# cpu.net
KiCad netlist of a schematic drawn in Altium Designer
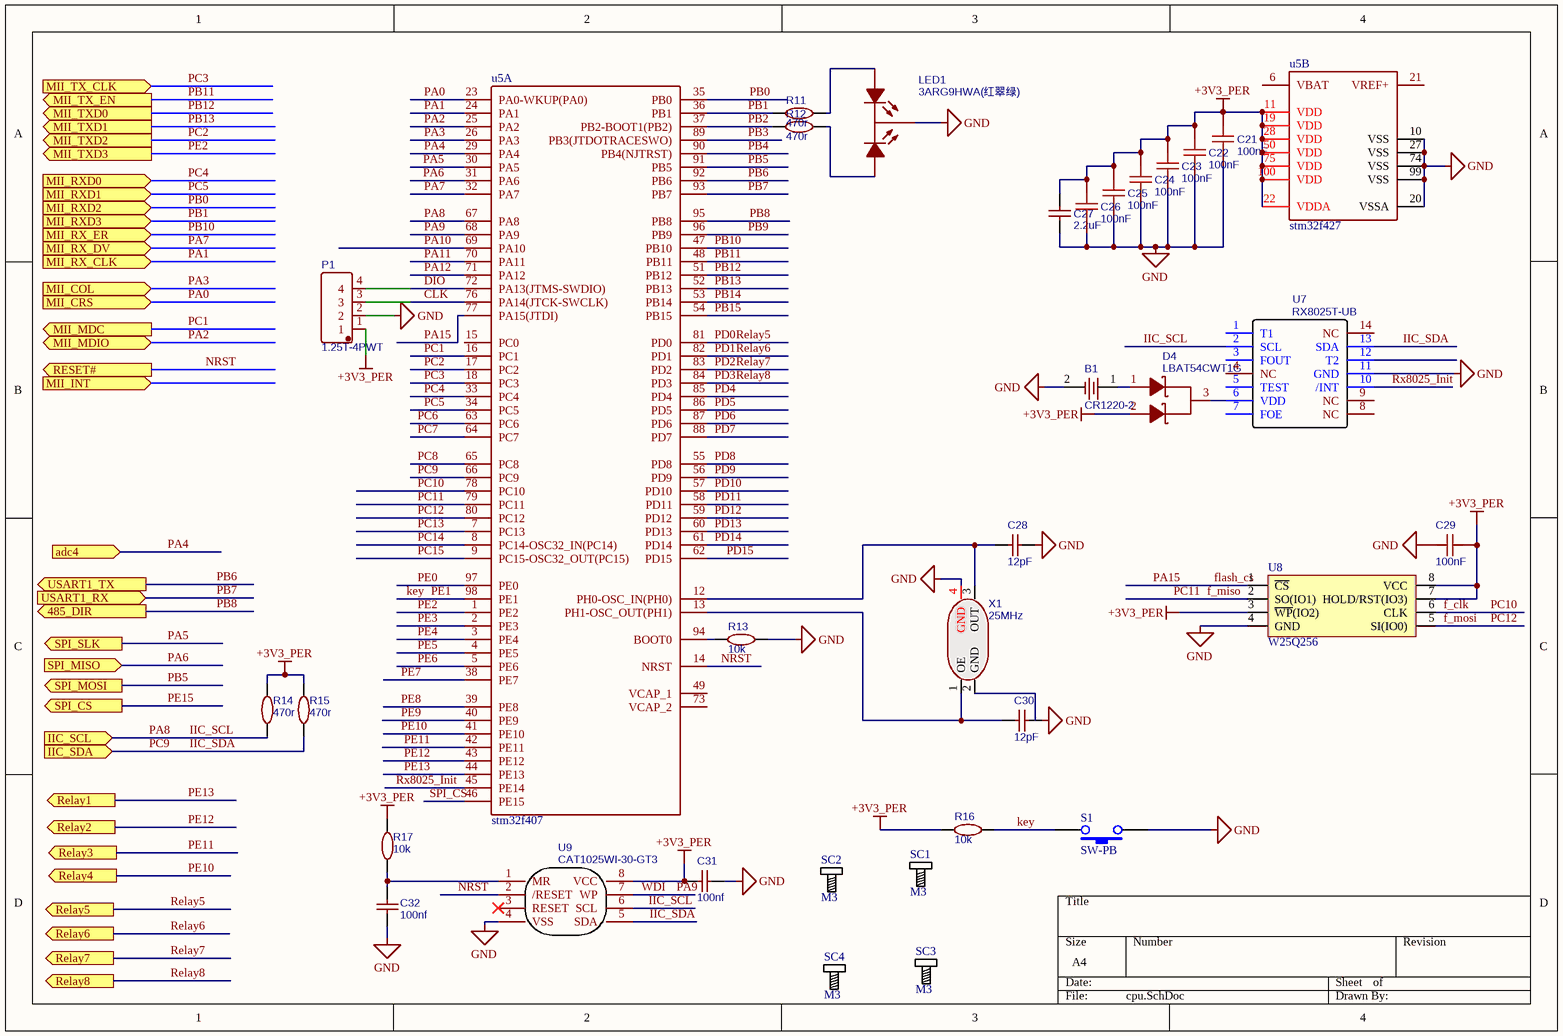
[diagram p0: cpu.SchDoc]

(export (version "E")
  (design (tool "Eeschema 10.0.6"))
  (components
    (comp (ref "B1") (value "CR1220-2") (footprint "BATTERY-2") (libsource (lib "") (part "root_2___3")))
    (comp (ref "C21")
      (value "100nF")
      (footprint "0603 - cap")
      (fields (field (name "BOM_MANUFACTURER PART") "CC0603KRX7R9BB104"))
      (libsource (lib "") (part "root_1___1"))
    )
    (comp (ref "C22")
      (value "100nF")
      (footprint "0603 - cap")
      (fields (field (name "BOM_MANUFACTURER PART") "CC0603KRX7R9BB104"))
      (libsource (lib "") (part "root_1___1"))
    )
    (comp (ref "C23")
      (value "100nF")
      (footprint "0603 - cap")
      (fields (field (name "BOM_MANUFACTURER PART") "CC0603KRX7R9BB104"))
      (libsource (lib "") (part "root_1___1"))
    )
    (comp (ref "C24")
      (value "100nF")
      (footprint "0603 - cap")
      (fields (field (name "BOM_MANUFACTURER PART") "CC0603KRX7R9BB104"))
      (libsource (lib "") (part "root_1___1"))
    )
    (comp (ref "C25")
      (value "100nF")
      (footprint "0603 - cap")
      (fields (field (name "BOM_MANUFACTURER PART") "CC0603KRX7R9BB104"))
      (libsource (lib "") (part "root_1___1"))
    )
    (comp (ref "C26")
      (value "100nF")
      (footprint "0603 - cap")
      (fields (field (name "BOM_MANUFACTURER PART") "CC0603KRX7R9BB104"))
      (libsource (lib "") (part "root_1___1"))
    )
    (comp (ref "C27")
      (value "2.2uF")
      (footprint "1206 - cap")
      (fields (field (name "BOM_MANUFACTURER PART") "CL31B225KBHNNNE"))
      (libsource (lib "altium-import") (part "root_1__"))
    )
    (comp (ref "C28")
      (value "12pF")
      (footprint "0603 - cap")
      (fields (field (name "BOM_MANUFACTURER PART") "CL10C120JB8NNNC"))
      (libsource (lib "altium-import") (part "root_2__"))
    )
    (comp (ref "C29")
      (value "100nF")
      (footprint "0603 - cap")
      (fields (field (name "BOM_MANUFACTURER PART") "CC0603KRX7R9BB104"))
      (libsource (lib "") (part "root_2___4"))
    )
    (comp (ref "C30")
      (value "12pF")
      (footprint "0603 - cap")
      (fields (field (name "BOM_MANUFACTURER PART") "CL10C120JB8NNNC"))
      (libsource (lib "altium-import") (part "root_2__"))
    )
    (comp (ref "C31")
      (value "100nf")
      (footprint "0603 - cap")
      (fields (field (name "BOM_MANUFACTURER PART") "CL10C120JB8NNNC"))
      (libsource (lib "") (part "root_0___1"))
    )
    (comp (ref "C32")
      (value "100nf")
      (footprint "0603 - cap")
      (fields (field (name "BOM_MANUFACTURER PART") "CL10C120JB8NNNC"))
      (libsource (lib "") (part "root_3___1"))
    )
    (comp (ref "D4")
      (value "LBAT54CWT1G")
      (footprint "SC-70(SC-70-3)")
      (libsource (lib "") (part "root_0___2"))
    )
    (comp (ref "LED1")
      (value "3ARG9HWA(红翠绿)")
      (footprint "led3")
      (libsource (lib "altium-import") (part "root_3__"))
    )
    (comp (ref "P1") (value "1.25T-4PWT") (footprint "1.25T-4PWT") (libsource (lib "") (part "root_2___2")))
    (comp (ref "R11")
      (value "470r")
      (footprint "0603-res")
      (fields (field (name "BOM_MANUFACTURER PART") "0603WAF1001T5E"))
      (libsource (lib "") (part "root_2___1"))
    )
    (comp (ref "R12")
      (value "470r")
      (footprint "0603-res")
      (fields (field (name "BOM_MANUFACTURER PART") "0603WAF1001T5E"))
      (libsource (lib "") (part "root_2___1"))
    )
    (comp (ref "R13")
      (value "10k")
      (footprint "0603-res")
      (fields (field (name "BOM_MANUFACTURER PART") "0603WAF1001T5E"))
      (libsource (lib "") (part "root_2___1"))
    )
    (comp (ref "R14")
      (value "470r")
      (footprint "0603-res")
      (fields (field (name "BOM_MANUFACTURER PART") "0603WAF1001T5E"))
      (libsource (lib "") (part "root_1___2"))
    )
    (comp (ref "R15")
      (value "470r")
      (footprint "0603-res")
      (fields (field (name "BOM_MANUFACTURER PART") "0603WAF1001T5E"))
      (libsource (lib "") (part "root_1___2"))
    )
    (comp (ref "R16")
      (value "10k")
      (footprint "0603-res")
      (fields (field (name "BOM_MANUFACTURER PART") "0603WAF1001T5E"))
      (libsource (lib "") (part "root_0___3"))
    )
    (comp (ref "R17")
      (value "10k")
      (footprint "0603-res")
      (fields (field (name "BOM_MANUFACTURER PART") "0603WAF1001T5E"))
      (libsource (lib "") (part "root_1___2"))
    )
    (comp (ref "S1")
      (value "SW-PB")
      (footprint "HYA45513")
      (description "微型按键开关")
      (libsource (lib "杂元件库") (part "SW-PB"))
    )
    (comp (ref "SC1")
      (value "M3")
      (footprint "安装孔(3mm)")
      (description "Screw")
      (libsource (lib "SCH_Mechanical") (part "Screw_M3"))
    )
    (comp (ref "SC2")
      (value "M3")
      (footprint "安装孔(3mm)")
      (description "Screw")
      (libsource (lib "SCH_Mechanical") (part "Screw_M3"))
    )
    (comp (ref "SC3")
      (value "M3")
      (footprint "安装孔(3mm)")
      (description "Screw")
      (libsource (lib "SCH_Mechanical") (part "Screw_M3"))
    )
    (comp (ref "SC4")
      (value "M3")
      (footprint "安装孔(3mm)")
      (description "Screw")
      (libsource (lib "SCH_Mechanical") (part "Screw_M3"))
    )
    (comp (ref "u5")
      (value "stm32f407")
      (footprint "LQFP-100_14X14X05P")
      (libsource (lib "TcpControl_1") (part "stm32f427"))
    )
    (comp (ref "U7")
      (value "RX8025T-UB")
      (footprint "SOP-14_208MIL")
      (libsource (lib "altium-import") (part "root_0__"))
    )
    (comp (ref "U8")
      (value "W25Q256")
      (footprint "LC-SOIC-8_208mil")
      (description "W25Q128")
      (libsource (lib "STM32F429核心板封装库") (part "W25Q128"))
    )
    (comp (ref "U9")
      (value "CAT1025WI-30-GT3")
      (footprint "SOIC-8_150MIL")
      (libsource (lib "") (part "root_0___4"))
    )
    (comp (ref "X1")
      (value "25MHz")
      (footprint "OSC-YSX-3225_4P")
      (fields (field (name "BOM_MANUFACTURER PART") "X322525MOB4SI"))
      (libsource (lib "") (part "root_1___3"))
    )
  )
  (nets
    (net (code "1") (name "+3V3_PER") (class "Default")
      (node (ref "C21") (pin "2") (pinfunction "2_2") (pintype "passive"))
      (node (ref "C22") (pin "2") (pinfunction "2_2") (pintype "passive"))
      (node (ref "C23") (pin "2") (pinfunction "2_2") (pintype "passive"))
      (node (ref "C24") (pin "2") (pinfunction "2_2") (pintype "passive"))
      (node (ref "C25") (pin "2") (pinfunction "2_2") (pintype "passive"))
      (node (ref "C26") (pin "2") (pinfunction "2_2") (pintype "passive"))
      (node (ref "C27") (pin "2") (pinfunction "2_2") (pintype "passive"))
      (node (ref "C29") (pin "1") (pinfunction "1_1") (pintype "passive"))
      (node (ref "C31") (pin "1") (pinfunction "1_1") (pintype "passive"))
      (node (ref "D4") (pin "2") (pinfunction "K2_2") (pintype "passive"))
      (node (ref "P1") (pin "1") (pinfunction "1_1") (pintype "passive"))
      (node (ref "R14") (pin "2") (pinfunction "2_2") (pintype "passive"))
      (node (ref "R15") (pin "2") (pinfunction "2_2") (pintype "passive"))
      (node (ref "R16") (pin "1") (pinfunction "1_1") (pintype "passive"))
      (node (ref "R17") (pin "2") (pinfunction "2_2") (pintype "passive"))
      (node (ref "U8") (pin "3") (pinfunction "~{WP}(IO2)_3") (pintype "passive"))
      (node (ref "U8") (pin "7") (pinfunction "HOLD/RST(IO3)_7") (pintype "power_in"))
      (node (ref "U8") (pin "8") (pinfunction "VCC_8") (pintype "passive"))
      (node (ref "U9") (pin "8") (pinfunction "VCC_8") (pintype "passive"))
      (node (ref "u5") (pin "100") (pinfunction "VDD_100") (pintype "passive"))
      (node (ref "u5") (pin "11") (pinfunction "VDD_11") (pintype "passive"))
      (node (ref "u5") (pin "19") (pinfunction "VDD_19") (pintype "passive"))
      (node (ref "u5") (pin "22") (pinfunction "VDDA_22") (pintype "passive"))
      (node (ref "u5") (pin "28") (pinfunction "VDD_28") (pintype "passive"))
      (node (ref "u5") (pin "50") (pinfunction "VDD_50") (pintype "passive"))
      (node (ref "u5") (pin "75") (pinfunction "VDD_75") (pintype "passive"))
    )
    (net (code "2") (name "/CLK") (class "Default")
      (node (ref "P1") (pin "3") (pinfunction "3_3") (pintype "passive"))
      (node (ref "u5") (pin "76") (pinfunction "PA14(JTCK-SWCLK)_76") (pintype "passive"))
    )
    (net (code "3") (name "/DIO") (class "Default")
      (node (ref "P1") (pin "4") (pinfunction "4_4") (pintype "passive"))
      (node (ref "u5") (pin "72") (pinfunction "PA13(JTMS-SWDIO)_72") (pintype "passive"))
    )
    (net (code "4") (name "/IIC_SCL") (class "Default")
      (node (ref "R14") (pin "1") (pinfunction "1_1") (pintype "passive"))
      (node (ref "U7") (pin "2") (pinfunction "SCL_2") (pintype "passive"))
      (node (ref "U9") (pin "6") (pinfunction "SCL_6") (pintype "passive"))
      (node (ref "u5") (pin "67") (pinfunction "PA8_67") (pintype "passive"))
    )
    (net (code "5") (name "/IIC_SDA") (class "Default")
      (node (ref "R15") (pin "1") (pinfunction "1_1") (pintype "passive"))
      (node (ref "U7") (pin "13") (pinfunction "SDA_13") (pintype "passive"))
      (node (ref "U9") (pin "5") (pinfunction "SDA_5") (pintype "passive"))
      (node (ref "u5") (pin "66") (pinfunction "PC9_66") (pintype "passive"))
    )
    (net (code "7") (name "/NRST") (class "Default")
      (node (ref "U9") (pin "2") (pinfunction "/RESET_2") (pintype "passive"))
      (node (ref "u5") (pin "14") (pinfunction "NRST_14") (pintype "passive"))
    )
    (net (code "8") (name "/PA0") (class "Default")
      (node (ref "u5") (pin "23") (pinfunction "PA0-WKUP(PA0)_23") (pintype "passive"))
    )
    (net (code "9") (name "/PA1") (class "Default")
      (node (ref "u5") (pin "24") (pinfunction "PA1_24") (pintype "passive"))
    )
    (net (code "10") (name "/PA2") (class "Default")
      (node (ref "u5") (pin "25") (pinfunction "PA2_25") (pintype "passive"))
    )
    (net (code "11") (name "/PA3") (class "Default")
      (node (ref "u5") (pin "26") (pinfunction "PA3_26") (pintype "passive"))
    )
    (net (code "12") (name "/PA4") (class "Default")
      (node (ref "u5") (pin "29") (pinfunction "PA4_29") (pintype "passive"))
    )
    (net (code "13") (name "/PA5") (class "Default")
      (node (ref "u5") (pin "30") (pinfunction "PA5_30") (pintype "passive"))
    )
    (net (code "14") (name "/PA6") (class "Default")
      (node (ref "u5") (pin "31") (pinfunction "PA6_31") (pintype "passive"))
    )
    (net (code "15") (name "/PA7") (class "Default")
      (node (ref "u5") (pin "32") (pinfunction "PA7_32") (pintype "passive"))
    )
    (net (code "16") (name "/PA9") (class "Default")
      (node (ref "U9") (pin "7") (pinfunction "WP_7") (pintype "passive"))
      (node (ref "u5") (pin "68") (pinfunction "PA9_68") (pintype "passive"))
    )
    (net (code "17") (name "/PA10") (class "Default")
      (node (ref "u5") (pin "69") (pinfunction "PA10_69") (pintype "passive"))
    )
    (net (code "18") (name "/PA11") (class "Default")
      (node (ref "u5") (pin "70") (pinfunction "PA11_70") (pintype "passive"))
    )
    (net (code "19") (name "/PA12") (class "Default")
      (node (ref "u5") (pin "71") (pinfunction "PA12_71") (pintype "passive"))
    )
    (net (code "20") (name "/PA15") (class "Default")
      (node (ref "U8") (pin "1") (pinfunction "~{CS}_1") (pintype "passive"))
      (node (ref "u5") (pin "77") (pinfunction "PA15(JTDI)_77") (pintype "passive"))
    )
    (net (code "21") (name "/PB0") (class "Default")
      (node (ref "u5") (pin "35") (pinfunction "PB0_35") (pintype "passive"))
    )
    (net (code "22") (name "/PB1") (class "Default")
      (node (ref "R11") (pin "2") (pinfunction "2_2") (pintype "passive"))
      (node (ref "u5") (pin "36") (pinfunction "PB1_36") (pintype "passive"))
    )
    (net (code "23") (name "/PB2") (class "Default")
      (node (ref "R12") (pin "2") (pinfunction "2_2") (pintype "passive"))
      (node (ref "u5") (pin "37") (pinfunction "PB2-BOOT1(PB2)_37") (pintype "passive"))
    )
    (net (code "24") (name "/PB3") (class "Default")
      (node (ref "u5") (pin "89") (pinfunction "PB3(JTDOTRACESWO)_89") (pintype "passive"))
    )
    (net (code "25") (name "/PB4") (class "Default")
      (node (ref "u5") (pin "90") (pinfunction "PB4(NJTRST)_90") (pintype "passive"))
    )
    (net (code "26") (name "/PB5") (class "Default")
      (node (ref "u5") (pin "91") (pinfunction "PB5_91") (pintype "passive"))
    )
    (net (code "27") (name "/PB6") (class "Default")
      (node (ref "u5") (pin "92") (pinfunction "PB6_92") (pintype "passive"))
    )
    (net (code "28") (name "/PB7") (class "Default")
      (node (ref "u5") (pin "93") (pinfunction "PB7_93") (pintype "passive"))
    )
    (net (code "29") (name "/PB8") (class "Default")
      (node (ref "u5") (pin "95") (pinfunction "PB8_95") (pintype "passive"))
    )
    (net (code "30") (name "/PB9") (class "Default")
      (node (ref "u5") (pin "96") (pinfunction "PB9_96") (pintype "passive"))
    )
    (net (code "31") (name "/PB10") (class "Default")
      (node (ref "u5") (pin "47") (pinfunction "PB10_47") (pintype "passive"))
    )
    (net (code "32") (name "/PB11") (class "Default")
      (node (ref "u5") (pin "48") (pinfunction "PB11_48") (pintype "passive"))
    )
    (net (code "33") (name "/PB12") (class "Default")
      (node (ref "u5") (pin "51") (pinfunction "PB12_51") (pintype "passive"))
    )
    (net (code "34") (name "/PB13") (class "Default")
      (node (ref "u5") (pin "52") (pinfunction "PB13_52") (pintype "passive"))
    )
    (net (code "35") (name "/PB14") (class "Default")
      (node (ref "u5") (pin "53") (pinfunction "PB14_53") (pintype "passive"))
    )
    (net (code "36") (name "/PB15") (class "Default")
      (node (ref "u5") (pin "54") (pinfunction "PB15_54") (pintype "passive"))
    )
    (net (code "37") (name "/PC1") (class "Default")
      (node (ref "u5") (pin "16") (pinfunction "PC1_16") (pintype "passive"))
    )
    (net (code "38") (name "/PC2") (class "Default")
      (node (ref "u5") (pin "17") (pinfunction "PC2_17") (pintype "passive"))
    )
    (net (code "39") (name "/PC3") (class "Default")
      (node (ref "u5") (pin "18") (pinfunction "PC3_18") (pintype "passive"))
    )
    (net (code "40") (name "/PC4") (class "Default")
      (node (ref "u5") (pin "33") (pinfunction "PC4_33") (pintype "passive"))
    )
    (net (code "41") (name "/PC5") (class "Default")
      (node (ref "u5") (pin "34") (pinfunction "PC5_34") (pintype "passive"))
    )
    (net (code "42") (name "/PC6") (class "Default")
      (node (ref "u5") (pin "63") (pinfunction "PC6_63") (pintype "passive"))
    )
    (net (code "43") (name "/PC7") (class "Default")
      (node (ref "u5") (pin "64") (pinfunction "PC7_64") (pintype "passive"))
    )
    (net (code "44") (name "/PC8") (class "Default")
      (node (ref "u5") (pin "65") (pinfunction "PC8_65") (pintype "passive"))
    )
    (net (code "45") (name "/PC10") (class "Default")
      (node (ref "U8") (pin "6") (pinfunction "CLK_6") (pintype "passive"))
      (node (ref "u5") (pin "78") (pinfunction "PC10_78") (pintype "passive"))
    )
    (net (code "46") (name "/PC11") (class "Default")
      (node (ref "U8") (pin "2") (pinfunction "SO(IO1)_2") (pintype "passive"))
      (node (ref "u5") (pin "79") (pinfunction "PC11_79") (pintype "passive"))
    )
    (net (code "47") (name "/PC12") (class "Default")
      (node (ref "U8") (pin "5") (pinfunction "SI(IO0)_5") (pintype "power_in"))
      (node (ref "u5") (pin "80") (pinfunction "PC12_80") (pintype "passive"))
    )
    (net (code "48") (name "/PC13") (class "Default")
      (node (ref "u5") (pin "7") (pinfunction "PC13_7") (pintype "passive"))
    )
    (net (code "49") (name "/PC14") (class "Default")
      (node (ref "u5") (pin "8") (pinfunction "PC14-OSC32_IN(PC14)_8") (pintype "passive"))
    )
    (net (code "50") (name "/PC15") (class "Default")
      (node (ref "u5") (pin "9") (pinfunction "PC15-OSC32_OUT(PC15)_9") (pintype "passive"))
    )
    (net (code "51") (name "/PD0") (class "Default")
      (node (ref "u5") (pin "81") (pinfunction "PD0_81") (pintype "passive"))
    )
    (net (code "52") (name "/PD1") (class "Default")
      (node (ref "u5") (pin "82") (pinfunction "PD1_82") (pintype "passive"))
    )
    (net (code "53") (name "/PD2") (class "Default")
      (node (ref "u5") (pin "83") (pinfunction "PD2_83") (pintype "passive"))
    )
    (net (code "54") (name "/PD3") (class "Default")
      (node (ref "u5") (pin "84") (pinfunction "PD3_84") (pintype "passive"))
    )
    (net (code "55") (name "/PD4") (class "Default")
      (node (ref "u5") (pin "85") (pinfunction "PD4_85") (pintype "passive"))
    )
    (net (code "56") (name "/PD5") (class "Default")
      (node (ref "u5") (pin "86") (pinfunction "PD5_86") (pintype "passive"))
    )
    (net (code "57") (name "/PD6") (class "Default")
      (node (ref "u5") (pin "87") (pinfunction "PD6_87") (pintype "passive"))
    )
    (net (code "58") (name "/PD7") (class "Default")
      (node (ref "u5") (pin "88") (pinfunction "PD7_88") (pintype "passive"))
    )
    (net (code "59") (name "/PD8") (class "Default")
      (node (ref "u5") (pin "55") (pinfunction "PD8_55") (pintype "passive"))
    )
    (net (code "60") (name "/PD9") (class "Default")
      (node (ref "u5") (pin "56") (pinfunction "PD9_56") (pintype "passive"))
    )
    (net (code "61") (name "/PD10") (class "Default")
      (node (ref "u5") (pin "57") (pinfunction "PD10_57") (pintype "passive"))
    )
    (net (code "62") (name "/PD11") (class "Default")
      (node (ref "u5") (pin "58") (pinfunction "PD11_58") (pintype "passive"))
    )
    (net (code "63") (name "/PD12") (class "Default")
      (node (ref "u5") (pin "59") (pinfunction "PD12_59") (pintype "passive"))
    )
    (net (code "64") (name "/PD13") (class "Default")
      (node (ref "u5") (pin "60") (pinfunction "PD13_60") (pintype "passive"))
    )
    (net (code "65") (name "/PD14") (class "Default")
      (node (ref "u5") (pin "61") (pinfunction "PD14_61") (pintype "passive"))
    )
    (net (code "66") (name "/PD15") (class "Default")
      (node (ref "u5") (pin "62") (pinfunction "PD15_62") (pintype "passive"))
    )
    (net (code "67") (name "/PE0") (class "Default")
      (node (ref "u5") (pin "97") (pinfunction "PE0_97") (pintype "passive"))
    )
    (net (code "68") (name "/PE1") (class "Default")
      (node (ref "R16") (pin "2") (pinfunction "2_2") (pintype "passive"))
      (node (ref "S1") (pin "2") (pinfunction "2_2") (pintype "passive"))
      (node (ref "u5") (pin "98") (pinfunction "PE1_98") (pintype "passive"))
    )
    (net (code "69") (name "/PE2") (class "Default")
      (node (ref "u5") (pin "1") (pinfunction "PE2_1") (pintype "passive"))
    )
    (net (code "70") (name "/PE3") (class "Default")
      (node (ref "u5") (pin "2") (pinfunction "PE3_2") (pintype "passive"))
    )
    (net (code "71") (name "/PE4") (class "Default")
      (node (ref "u5") (pin "3") (pinfunction "PE4_3") (pintype "passive"))
    )
    (net (code "72") (name "/PE5") (class "Default")
      (node (ref "u5") (pin "4") (pinfunction "PE5_4") (pintype "passive"))
    )
    (net (code "73") (name "/PE6") (class "Default")
      (node (ref "u5") (pin "5") (pinfunction "PE6_5") (pintype "passive"))
    )
    (net (code "74") (name "/PE7") (class "Default")
      (node (ref "u5") (pin "38") (pinfunction "PE7_38") (pintype "passive"))
    )
    (net (code "75") (name "/PE8") (class "Default")
      (node (ref "u5") (pin "39") (pinfunction "PE8_39") (pintype "passive"))
    )
    (net (code "76") (name "/PE9") (class "Default")
      (node (ref "u5") (pin "40") (pinfunction "PE9_40") (pintype "passive"))
    )
    (net (code "77") (name "/PE10") (class "Default")
      (node (ref "u5") (pin "41") (pinfunction "PE10_41") (pintype "passive"))
    )
    (net (code "78") (name "/PE11") (class "Default")
      (node (ref "u5") (pin "42") (pinfunction "PE11_42") (pintype "passive"))
    )
    (net (code "79") (name "/PE12") (class "Default")
      (node (ref "u5") (pin "43") (pinfunction "PE12_43") (pintype "passive"))
    )
    (net (code "80") (name "/PE13") (class "Default")
      (node (ref "u5") (pin "44") (pinfunction "PE13_44") (pintype "passive"))
    )
    (net (code "81") (name "/PE15") (class "Default")
      (node (ref "u5") (pin "46") (pinfunction "PE15_46") (pintype "passive"))
    )
    (net (code "82") (name "/Rx8025_Init") (class "Default")
      (node (ref "U7") (pin "10") (pinfunction "/INT_10") (pintype "passive"))
      (node (ref "u5") (pin "45") (pinfunction "PE14_45") (pintype "passive"))
    )
    (net (code "83") (name "GND") (class "Default")
      (node (ref "B1") (pin "2") (pinfunction "2_2") (pintype "passive"))
      (node (ref "C21") (pin "1") (pinfunction "1_1") (pintype "passive"))
      (node (ref "C22") (pin "1") (pinfunction "1_1") (pintype "passive"))
      (node (ref "C23") (pin "1") (pinfunction "1_1") (pintype "passive"))
      (node (ref "C24") (pin "1") (pinfunction "1_1") (pintype "passive"))
      (node (ref "C25") (pin "1") (pinfunction "1_1") (pintype "passive"))
      (node (ref "C26") (pin "1") (pinfunction "1_1") (pintype "passive"))
      (node (ref "C27") (pin "1") (pinfunction "1_1") (pintype "passive"))
      (node (ref "C28") (pin "1") (pinfunction "1_1") (pintype "passive"))
      (node (ref "C29") (pin "2") (pinfunction "2_2") (pintype "passive"))
      (node (ref "C30") (pin "1") (pinfunction "1_1") (pintype "passive"))
      (node (ref "C31") (pin "2") (pinfunction "2_2") (pintype "passive"))
      (node (ref "C32") (pin "2") (pinfunction "2_2") (pintype "passive"))
      (node (ref "LED1") (pin "3") (pinfunction "K_3") (pintype "passive"))
      (node (ref "P1") (pin "2") (pinfunction "2_2") (pintype "passive"))
      (node (ref "R13") (pin "1") (pinfunction "1_1") (pintype "passive"))
      (node (ref "S1") (pin "1") (pinfunction "1_1") (pintype "passive"))
      (node (ref "U7") (pin "11") (pinfunction "GND_11") (pintype "passive"))
      (node (ref "U8") (pin "4") (pinfunction "GND_4") (pintype "passive"))
      (node (ref "U9") (pin "4") (pinfunction "VSS_4") (pintype "passive"))
      (node (ref "X1") (pin "4") (pinfunction "GND_4") (pintype "passive"))
      (node (ref "u5") (pin "10") (pinfunction "VSS_10") (pintype "passive"))
      (node (ref "u5") (pin "20") (pinfunction "VSSA_20") (pintype "passive"))
      (node (ref "u5") (pin "27") (pinfunction "VSS_27") (pintype "passive"))
      (node (ref "u5") (pin "74") (pinfunction "VSS_74") (pintype "passive"))
      (node (ref "u5") (pin "99") (pinfunction "VSS_99") (pintype "passive"))
    )
    (net (code "84") (name "Net-(D4-A)") (class "Default")
      (node (ref "D4") (pin "3") (pinfunction "A_3") (pintype "passive"))
      (node (ref "U7") (pin "6") (pinfunction "VDD_6") (pintype "passive"))
    )
    (net (code "85") (name "Net-(D4-K1)") (class "Default")
      (node (ref "B1") (pin "1") (pinfunction "1_1") (pintype "passive"))
      (node (ref "D4") (pin "1") (pinfunction "K1_1") (pintype "passive"))
    )
    (net (code "86") (name "Net-(LED1-A1)") (class "Default")
      (node (ref "LED1") (pin "1") (pinfunction "A1_1") (pintype "passive"))
      (node (ref "R11") (pin "1") (pinfunction "1_1") (pintype "passive"))
    )
    (net (code "87") (name "Net-(LED1-A2)") (class "Default")
      (node (ref "LED1") (pin "2") (pinfunction "A2_2") (pintype "passive"))
      (node (ref "R12") (pin "1") (pinfunction "1_1") (pintype "passive"))
    )
    (net (code "88") (name "Net-(U9-MR)") (class "Default")
      (node (ref "C32") (pin "1") (pinfunction "1_1") (pintype "passive"))
      (node (ref "R17") (pin "1") (pinfunction "1_1") (pintype "passive"))
      (node (ref "U9") (pin "1") (pinfunction "MR_1") (pintype "passive"))
    )
    (net (code "89") (name "Net-(X1-OE)") (class "Default")
      (node (ref "C30") (pin "2") (pinfunction "2_2") (pintype "passive"))
      (node (ref "X1") (pin "1") (pinfunction "OE_1") (pintype "passive"))
      (node (ref "u5") (pin "13") (pinfunction "PH1-OSC_OUT(PH1)_13") (pintype "passive"))
    )
    (net (code "90") (name "Net-(X1-OUT)") (class "Default")
      (node (ref "C28") (pin "2") (pinfunction "2_2") (pintype "passive"))
      (node (ref "X1") (pin "3") (pinfunction "OUT_3") (pintype "passive"))
      (node (ref "u5") (pin "12") (pinfunction "PH0-OSC_IN(PH0)_12") (pintype "passive"))
    )
    (net (code "91") (name "Net-(u5A-BOOT0)") (class "Default")
      (node (ref "R13") (pin "2") (pinfunction "2_2") (pintype "passive"))
      (node (ref "u5") (pin "94") (pinfunction "BOOT0_94") (pintype "passive"))
    )
    (net (code "92") (name "unconnected-(U7-FOE-Pad7)") (class "Default")
      (node (ref "U7") (pin "7") (pinfunction "FOE_7") (pintype "passive"))
    )
    (net (code "93") (name "unconnected-(U7-FOUT-Pad3)") (class "Default")
      (node (ref "U7") (pin "3") (pinfunction "FOUT_3") (pintype "passive"))
    )
    (net (code "94") (name "unconnected-(U7-NC-Pad4)") (class "Default")
      (node (ref "U7") (pin "4") (pinfunction "NC_4") (pintype "passive"))
    )
    (net (code "95") (name "unconnected-(U7-NC-Pad8)") (class "Default")
      (node (ref "U7") (pin "8") (pinfunction "NC_8") (pintype "passive"))
    )
    (net (code "96") (name "unconnected-(U7-NC-Pad9)") (class "Default")
      (node (ref "U7") (pin "9") (pinfunction "NC_9") (pintype "passive"))
    )
    (net (code "97") (name "unconnected-(U7-NC-Pad14)") (class "Default")
      (node (ref "U7") (pin "14") (pinfunction "NC_14") (pintype "passive"))
    )
    (net (code "98") (name "unconnected-(U7-T1-Pad1)") (class "Default")
      (node (ref "U7") (pin "1") (pinfunction "T1_1") (pintype "passive"))
    )
    (net (code "99") (name "unconnected-(U7-T2-Pad12)") (class "Default")
      (node (ref "U7") (pin "12") (pinfunction "T2_12") (pintype "passive"))
    )
    (net (code "100") (name "unconnected-(U7-TEST-Pad5)") (class "Default")
      (node (ref "U7") (pin "5") (pinfunction "TEST_5") (pintype "passive"))
    )
    (net (code "101") (name "unconnected-(U9-RESET-Pad3)") (class "Default")
      (node (ref "U9") (pin "3") (pinfunction "RESET_3") (pintype "passive+no_connect"))
    )
    (net (code "102") (name "unconnected-(X1-GND-Pad2)") (class "Default")
      (node (ref "X1") (pin "2") (pinfunction "GND_2") (pintype "passive"))
    )
    (net (code "103") (name "unconnected-(u5A-PC0-Pad15)") (class "Default")
      (node (ref "u5") (pin "15") (pinfunction "PC0_15") (pintype "passive"))
    )
    (net (code "104") (name "unconnected-(u5A-VCAP_1-Pad49)") (class "Default")
      (node (ref "u5") (pin "49") (pinfunction "VCAP_1_49") (pintype "passive"))
    )
    (net (code "105") (name "unconnected-(u5A-VCAP_2-Pad73)") (class "Default")
      (node (ref "u5") (pin "73") (pinfunction "VCAP_2_73") (pintype "passive"))
    )
    (net (code "106") (name "unconnected-(u5B-VBAT-Pad6)") (class "Default")
      (node (ref "u5") (pin "6") (pinfunction "VBAT_6") (pintype "passive"))
    )
    (net (code "107") (name "unconnected-(u5B-VREF+-Pad21)") (class "Default")
      (node (ref "u5") (pin "21") (pinfunction "VREF+_21") (pintype "passive"))
    )
  )
)
